# Capx4.net
KiCad netlist of a schematic drawn in Altium Designer
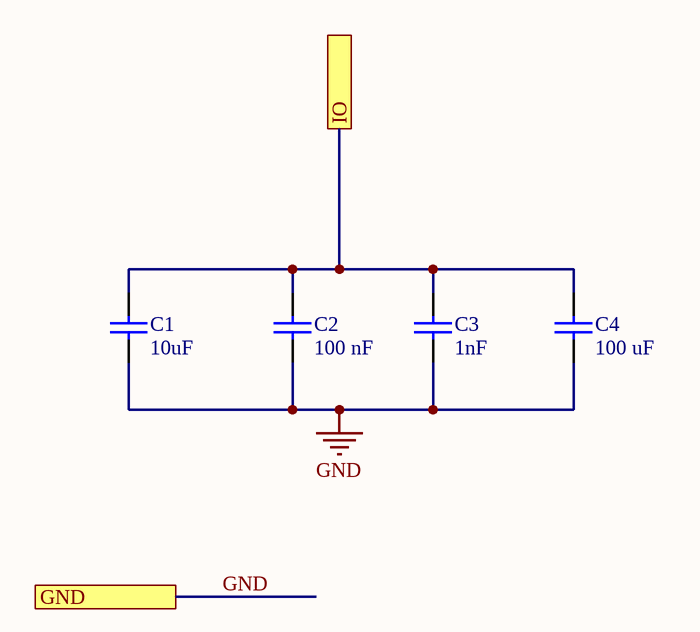
[diagram p0: Capx4.SchDoc]

(export (version "E")
  (design (tool "Eeschema 10.0.6"))
  (components
    (comp (ref "C1")
      (value "10uF")
      (footprint "KEMET C0805C106K4PACTU")
      (description "CAP CER 10UF 16V X5R 0805\r\n±10% 16V Ceramic Capacitor X5R 0805 (2012 Metric)")
      (fields (field (name "Comment") "Cap 10uF 0805"))
      (libsource (lib "IFAT6") (part "Cap 10uF 0805"))
    )
    (comp (ref "C2")
      (value "100 nF")
      (footprint "KEMET C0805C104J8RACTU")
      (description "CAP CER 0.1UF 10V X7R 0805\r\n±10% 10V Ceramic Capacitor X7R 0805 (2012 Metric)")
      (fields (field (name "Comment") "Cap 100nF 0805"))
      (libsource (lib "IFAT6") (part "Cap 100nF 0805"))
    )
    (comp (ref "C3")
      (value "1nF")
      (footprint "Samsung CL21B Series")
      (fields (field (name "Comment") "Cap 1nF 0805"))
      (libsource (lib "IFAT6") (part "Cap 1nF 0805"))
    )
    (comp (ref "C4")
      (value "100 uF")
      (footprint "KEMET C0805C104J8RACTU")
      (description "100 µF ±20% 6.3V Ceramic Capacitor X5R 0805 (2012 Metric)")
      (fields (field (name "Comment") "Cap 100uF 0805"))
      (libsource (lib "IFAT6") (part "Cap 100uF 0805"))
    )
  )
  (nets
    (net (code "1") (name "/IO") (class "Default")
      (node (ref "C1") (pin "1") (pinfunction "1_1") (pintype "passive"))
      (node (ref "C2") (pin "1") (pinfunction "1_1") (pintype "passive"))
      (node (ref "C3") (pin "1") (pinfunction "1_1") (pintype "passive"))
      (node (ref "C4") (pin "1") (pinfunction "1_1") (pintype "passive"))
    )
    (net (code "2") (name "GND") (class "Default")
      (node (ref "C1") (pin "2") (pinfunction "2_2") (pintype "passive"))
      (node (ref "C2") (pin "2") (pinfunction "2_2") (pintype "passive"))
      (node (ref "C3") (pin "2") (pinfunction "2_2") (pintype "passive"))
      (node (ref "C4") (pin "2") (pinfunction "2_2") (pintype "passive"))
    )
  )
)
